# Tiny_Programmer.net
KiCad netlist of a schematic drawn in EAGLE
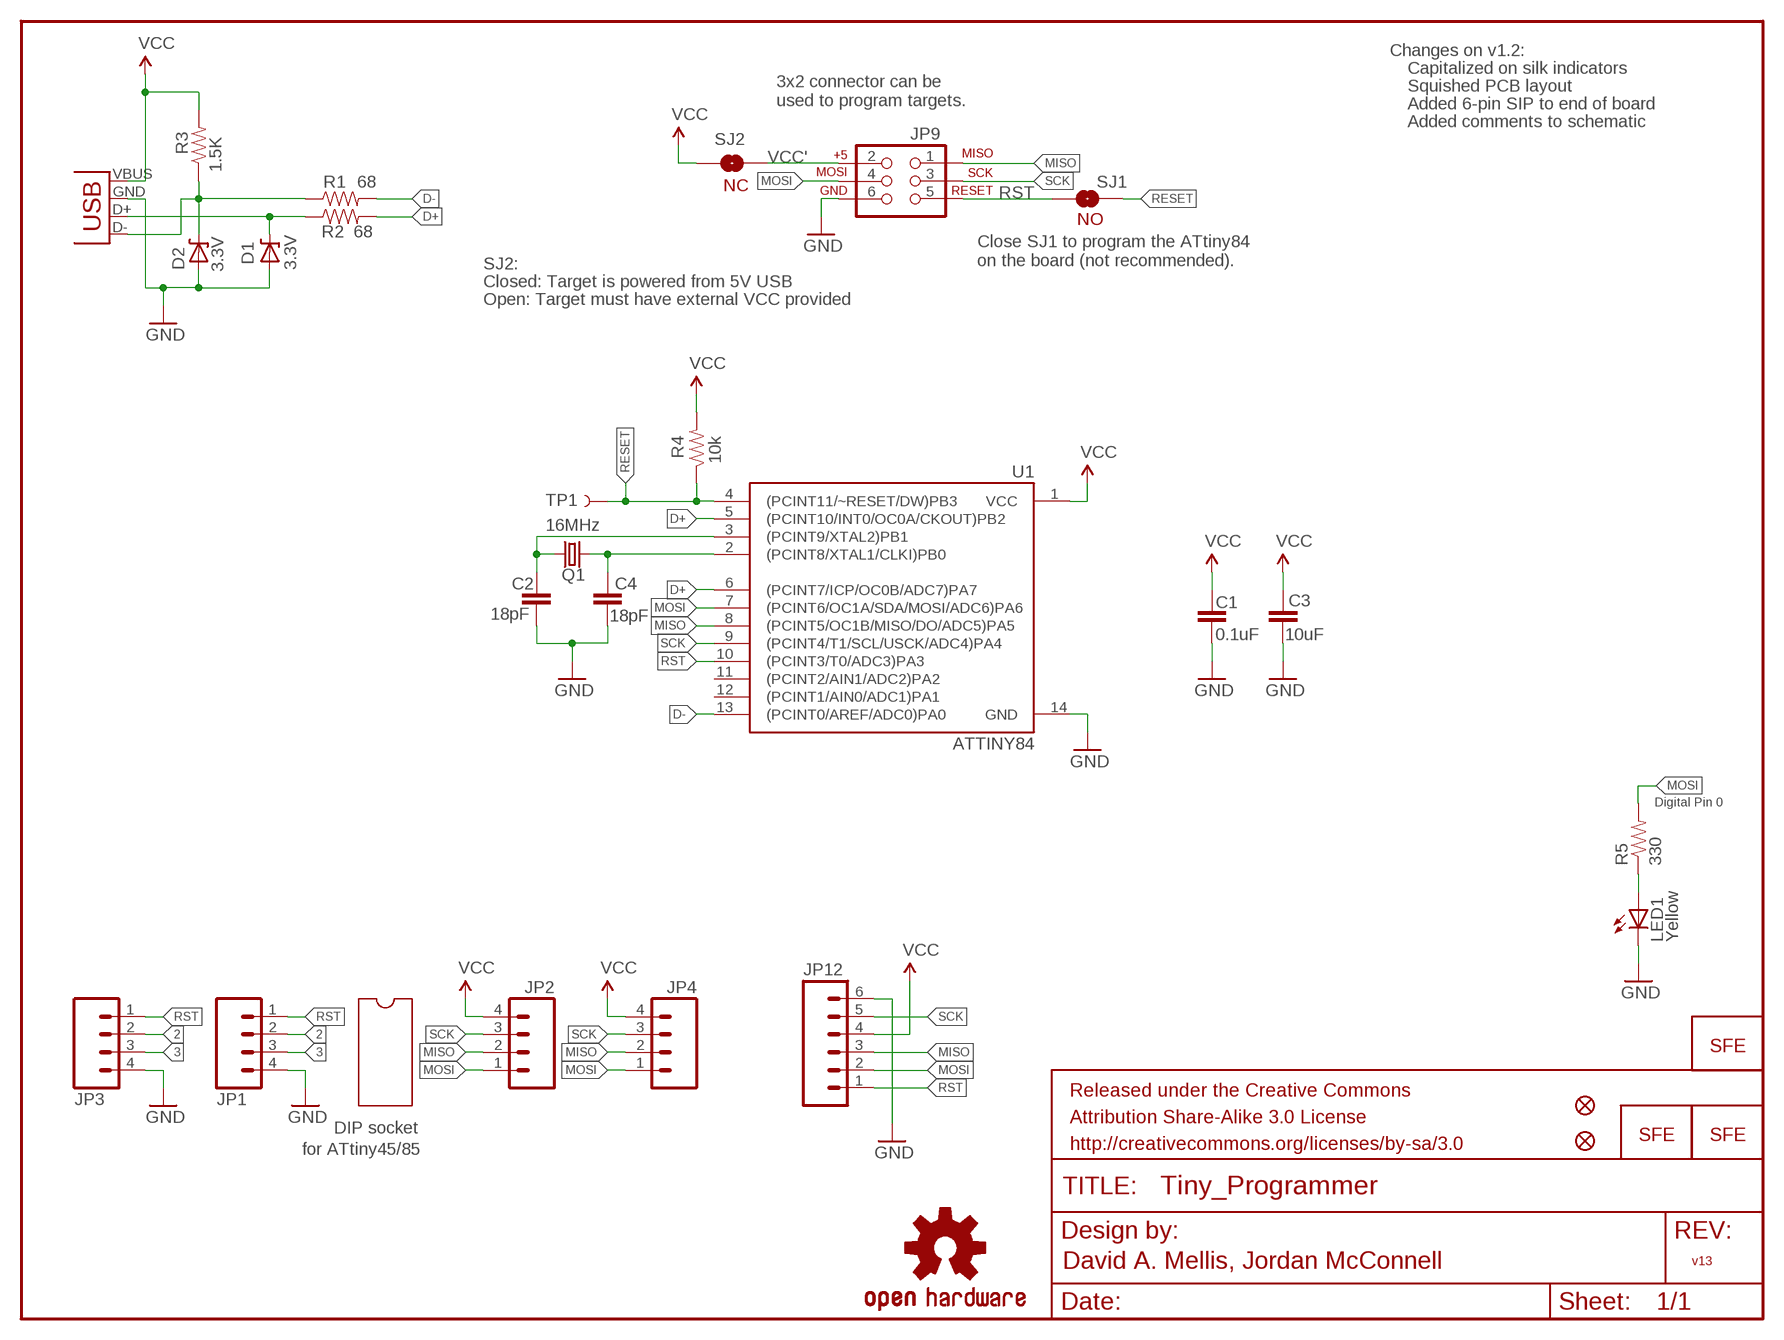
[diagram p0: schematic, sheet 1]

(export (version "E")
  (design (tool "Eeschema 10.0.6"))
  (components
    (comp (ref "C1")
      (value "0.1uF")
      (footprint "eagle-import:0402-CAP")
      (libsource (lib "eagle-import") (part "CAP0402-CAP"))
    )
    (comp (ref "C2")
      (value "18pF")
      (footprint "eagle-import:0402-CAP")
      (libsource (lib "eagle-import") (part "CAP0402-CAP"))
    )
    (comp (ref "C3")
      (value "10uF")
      (footprint "eagle-import:0402-CAP")
      (libsource (lib "eagle-import") (part "CAP0402-CAP"))
    )
    (comp (ref "C4")
      (value "18pF")
      (footprint "eagle-import:0402-CAP")
      (libsource (lib "eagle-import") (part "CAP0402-CAP"))
    )
    (comp (ref "D1")
      (value "3.3V")
      (footprint "eagle-import:SOD-323")
      (libsource (lib "eagle-import") (part "DIODE-ZENER-BZT52"))
    )
    (comp (ref "D2")
      (value "3.3V")
      (footprint "eagle-import:SOD-323")
      (libsource (lib "eagle-import") (part "DIODE-ZENER-BZT52"))
    )
    (comp (ref "FRAME1")
      (value "FRAME-LETTER")
      (footprint "eagle-import:CREATIVE_COMMONS")
      (libsource (lib "eagle-import") (part "FRAME-LETTER"))
    )
    (comp (ref "JP1")
      (value "M04PTH")
      (footprint "eagle-import:1X04")
      (libsource (lib "eagle-import") (part "M04PTH"))
    )
    (comp (ref "JP2")
      (value "M04PTH")
      (footprint "eagle-import:1X04")
      (libsource (lib "eagle-import") (part "M04PTH"))
    )
    (comp (ref "JP3")
      (value "M04SMD_STRAIGHT_COMBO")
      (footprint "eagle-import:1X04_SMD_STRAIGHT_COMBO")
      (libsource (lib "eagle-import") (part "M04SMD_STRAIGHT_COMBO"))
    )
    (comp (ref "JP4")
      (value "M04SMD_STRAIGHT_COMBO")
      (footprint "eagle-import:1X04_SMD_STRAIGHT_COMBO")
      (libsource (lib "eagle-import") (part "M04SMD_STRAIGHT_COMBO"))
    )
    (comp (ref "JP5")
      (value "LOGO-SFENW2")
      (footprint "eagle-import:SFE-NEW-WEB")
      (libsource (lib "eagle-import") (part "LOGO-SFENW2"))
    )
    (comp (ref "JP6")
      (value "LOGO-SFESK")
      (footprint "eagle-import:SFE-LOGO-FLAME")
      (libsource (lib "eagle-import") (part "LOGO-SFESK"))
    )
    (comp (ref "JP7")
      (value "FIDUCIALUFIDUCIAL")
      (footprint "eagle-import:MICRO-FIDUCIAL")
      (libsource (lib "eagle-import") (part "FIDUCIALUFIDUCIAL"))
    )
    (comp (ref "JP8")
      (value "FIDUCIALUFIDUCIAL")
      (footprint "eagle-import:MICRO-FIDUCIAL")
      (libsource (lib "eagle-import") (part "FIDUCIALUFIDUCIAL"))
    )
    (comp (ref "JP9")
      (value "AVR_SPI_PRG_6PTH")
      (footprint "eagle-import:2X3")
      (libsource (lib "eagle-import") (part "AVR_SPI_PRG_6PTH"))
    )
    (comp (ref "JP11")
      (value "LOGO-SFESK")
      (footprint "eagle-import:SFE-LOGO-FLAME")
      (libsource (lib "eagle-import") (part "LOGO-SFESK"))
    )
    (comp (ref "JP12")
      (value "M06SIP")
      (footprint "eagle-import:1X06")
      (libsource (lib "eagle-import") (part "M06SIP"))
    )
    (comp (ref "LED1")
      (value "Yellow")
      (footprint "eagle-import:LED-0603")
      (libsource (lib "eagle-import") (part "LED0603"))
    )
    (comp (ref "Q1")
      (value "16MHz")
      (footprint "eagle-import:CRYSTAL-SMD-5X3")
      (libsource (lib "eagle-import") (part "CRYSTAL5X3"))
    )
    (comp (ref "R1")
      (value "68")
      (footprint "eagle-import:0402-RES")
      (libsource (lib "eagle-import") (part "RESISTOR0402-RES"))
    )
    (comp (ref "R2")
      (value "68")
      (footprint "eagle-import:0402-RES")
      (libsource (lib "eagle-import") (part "RESISTOR0402-RES"))
    )
    (comp (ref "R3")
      (value "1.5K")
      (footprint "eagle-import:0402-RES")
      (libsource (lib "eagle-import") (part "RESISTOR0402-RES"))
    )
    (comp (ref "R4")
      (value "10k")
      (footprint "eagle-import:0402-RES")
      (libsource (lib "eagle-import") (part "RESISTOR0402-RES"))
    )
    (comp (ref "R5")
      (value "330")
      (footprint "eagle-import:0402-RES")
      (libsource (lib "eagle-import") (part "RESISTOR0402-RES"))
    )
    (comp (ref "SJ1")
      (value "SOLDERJUMPERNO")
      (footprint "eagle-import:SJ_2S-NO")
      (libsource (lib "eagle-import") (part "SOLDERJUMPERNO"))
    )
    (comp (ref "SJ2")
      (value "NC")
      (footprint "eagle-import:SJ_2S")
      (libsource (lib "eagle-import") (part "SOLDERJUMPERNC"))
    )
    (comp (ref "TP1")
      (value "TEST-POINT3")
      (footprint "eagle-import:PAD.03X.03")
      (libsource (lib "eagle-import") (part "TEST-POINT3"))
    )
    (comp (ref "U$1")
      (value "OSHW-LOGOS")
      (footprint "eagle-import:OSHW-LOGO-S")
      (libsource (lib "eagle-import") (part "OSHW-LOGOS"))
    )
    (comp (ref "U1")
      (value "ATTINY84")
      (footprint "eagle-import:SO14")
      (libsource (lib "eagle-import") (part "ATTINY84"))
    )
    (comp (ref "X1")
      (value "USB-A-H")
      (footprint "eagle-import:USB-A-H")
      (libsource (lib "eagle-import") (part "USB-A-H"))
    )
  )
  (nets
    (net (code "1") (name "/VCC'") (class "Default")
      (node (ref "JP9") (pin "2") (pinfunction "2_2") (pintype "passive"))
      (node (ref "SJ2") (pin "2") (pinfunction "2_2") (pintype "passive"))
    )
    (net (code "2") (name "2") (class "Default")
      (node (ref "JP1") (pin "2") (pinfunction "2_2") (pintype "passive"))
      (node (ref "JP3") (pin "2") (pinfunction "2_2") (pintype "passive"))
    )
    (net (code "3") (name "3") (class "Default")
      (node (ref "JP1") (pin "3") (pinfunction "3_3") (pintype "passive"))
      (node (ref "JP3") (pin "3") (pinfunction "3_3") (pintype "passive"))
    )
    (net (code "4") (name "D+") (class "Default")
      (node (ref "R2") (pin "2") (pinfunction "2_2") (pintype "passive"))
      (node (ref "U1") (pin "5") (pinfunction "(PCINT10/INT0/OC0A/CKOUT)PB2_5") (pintype "bidirectional"))
      (node (ref "U1") (pin "6") (pinfunction "(PCINT7/ICP/OC0B/ADC7)PA7_6") (pintype "bidirectional"))
    )
    (net (code "5") (name "D-") (class "Default")
      (node (ref "R1") (pin "2") (pinfunction "2_2") (pintype "passive"))
      (node (ref "U1") (pin "13") (pinfunction "(PCINT0/AREF/ADC0)PA0_13") (pintype "bidirectional"))
    )
    (net (code "6") (name "GND") (class "Default")
      (node (ref "C1") (pin "2") (pinfunction "2_2") (pintype "passive"))
      (node (ref "C2") (pin "2") (pinfunction "2_2") (pintype "passive"))
      (node (ref "C3") (pin "2") (pinfunction "2_2") (pintype "passive"))
      (node (ref "C4") (pin "2") (pinfunction "2_2") (pintype "passive"))
      (node (ref "D1") (pin "2") (pinfunction "A_2") (pintype "passive"))
      (node (ref "D2") (pin "2") (pinfunction "A_2") (pintype "passive"))
      (node (ref "JP1") (pin "4") (pinfunction "4_4") (pintype "passive"))
      (node (ref "JP12") (pin "6") (pinfunction "6_6") (pintype "passive"))
      (node (ref "JP3") (pin "4") (pinfunction "4_4") (pintype "passive"))
      (node (ref "JP9") (pin "6") (pinfunction "6_6") (pintype "passive"))
      (node (ref "LED1") (pin "C") (pinfunction "C_C") (pintype "passive"))
      (node (ref "U1") (pin "14") (pinfunction "GND_14") (pintype "bidirectional"))
      (node (ref "X1") (pin "GND") (pinfunction "VBUS_GND") (pintype "bidirectional"))
    )
    (net (code "7") (name "MISO") (class "Default")
      (node (ref "JP12") (pin "3") (pinfunction "3_3") (pintype "passive"))
      (node (ref "JP2") (pin "2") (pinfunction "2_2") (pintype "passive"))
      (node (ref "JP4") (pin "2") (pinfunction "2_2") (pintype "passive"))
      (node (ref "JP9") (pin "1") (pinfunction "1_1") (pintype "passive"))
      (node (ref "U1") (pin "8") (pinfunction "(PCINT5/OC1B/MISO/DO/ADC5)PA5_8") (pintype "bidirectional"))
    )
    (net (code "8") (name "MOSI") (class "Default")
      (node (ref "JP12") (pin "2") (pinfunction "2_2") (pintype "passive"))
      (node (ref "JP2") (pin "1") (pinfunction "1_1") (pintype "passive"))
      (node (ref "JP4") (pin "1") (pinfunction "1_1") (pintype "passive"))
      (node (ref "JP9") (pin "4") (pinfunction "4_4") (pintype "passive"))
      (node (ref "R5") (pin "2") (pinfunction "2_2") (pintype "passive"))
      (node (ref "U1") (pin "7") (pinfunction "(PCINT6/OC1A/SDA/MOSI/ADC6)PA6_7") (pintype "bidirectional"))
    )
    (net (code "9") (name "Net-(D1-C)") (class "Default")
      (node (ref "D1") (pin "1") (pinfunction "C_1") (pintype "passive"))
      (node (ref "R2") (pin "1") (pinfunction "1_1") (pintype "passive"))
      (node (ref "X1") (pin "D+") (pinfunction "D-_D+") (pintype "bidirectional"))
    )
    (net (code "10") (name "Net-(D2-C)") (class "Default")
      (node (ref "D2") (pin "1") (pinfunction "C_1") (pintype "passive"))
      (node (ref "R1") (pin "1") (pinfunction "1_1") (pintype "passive"))
      (node (ref "R3") (pin "1") (pinfunction "1_1") (pintype "passive"))
      (node (ref "X1") (pin "D-") (pinfunction "D+_D-") (pintype "bidirectional"))
    )
    (net (code "11") (name "Net-(LED1-PadA)") (class "Default")
      (node (ref "LED1") (pin "A") (pinfunction "A_A") (pintype "passive"))
      (node (ref "R5") (pin "1") (pinfunction "1_1") (pintype "passive"))
    )
    (net (code "12") (name "Net-(Q1-2)") (class "Default")
      (node (ref "C2") (pin "1") (pinfunction "1_1") (pintype "passive"))
      (node (ref "Q1") (pin "3") (pinfunction "2_3") (pintype "passive"))
      (node (ref "U1") (pin "3") (pinfunction "(PCINT9/XTAL2)PB1_3") (pintype "bidirectional"))
    )
    (net (code "13") (name "Net-(U1-(PCINT8{slash}XTAL1{slash}CLKI)PB0)") (class "Default")
      (node (ref "C4") (pin "1") (pinfunction "1_1") (pintype "passive"))
      (node (ref "Q1") (pin "1") (pinfunction "1_1") (pintype "passive"))
      (node (ref "U1") (pin "2") (pinfunction "(PCINT8/XTAL1/CLKI)PB0_2") (pintype "bidirectional"))
    )
    (net (code "14") (name "RESET") (class "Default")
      (node (ref "R4") (pin "1") (pinfunction "1_1") (pintype "passive"))
      (node (ref "SJ1") (pin "1") (pinfunction "1_1") (pintype "passive"))
      (node (ref "TP1") (pin "P$1") (pinfunction "1_P$1") (pintype "bidirectional"))
      (node (ref "U1") (pin "4") (pinfunction "(PCINT11/~{RESET/DW})PB3_4") (pintype "bidirectional"))
    )
    (net (code "15") (name "RST") (class "Default")
      (node (ref "JP1") (pin "1") (pinfunction "1_1") (pintype "passive"))
      (node (ref "JP12") (pin "1") (pinfunction "1_1") (pintype "passive"))
      (node (ref "JP3") (pin "1") (pinfunction "1_1") (pintype "passive"))
      (node (ref "JP9") (pin "5") (pinfunction "5_5") (pintype "passive"))
      (node (ref "SJ1") (pin "2") (pinfunction "2_2") (pintype "passive"))
      (node (ref "U1") (pin "10") (pinfunction "(PCINT3/T0/ADC3)PA3_10") (pintype "bidirectional"))
    )
    (net (code "16") (name "SCK") (class "Default")
      (node (ref "JP12") (pin "5") (pinfunction "5_5") (pintype "passive"))
      (node (ref "JP2") (pin "3") (pinfunction "3_3") (pintype "passive"))
      (node (ref "JP4") (pin "3") (pinfunction "3_3") (pintype "passive"))
      (node (ref "JP9") (pin "3") (pinfunction "3_3") (pintype "passive"))
      (node (ref "U1") (pin "9") (pinfunction "(PCINT4/T1/SCL/USCK/ADC4)PA4_9") (pintype "bidirectional"))
    )
    (net (code "17") (name "VCC") (class "Default")
      (node (ref "C1") (pin "1") (pinfunction "1_1") (pintype "passive"))
      (node (ref "C3") (pin "1") (pinfunction "1_1") (pintype "passive"))
      (node (ref "JP12") (pin "4") (pinfunction "4_4") (pintype "passive"))
      (node (ref "JP2") (pin "4") (pinfunction "4_4") (pintype "passive"))
      (node (ref "JP4") (pin "4") (pinfunction "4_4") (pintype "passive"))
      (node (ref "R3") (pin "2") (pinfunction "2_2") (pintype "passive"))
      (node (ref "R4") (pin "2") (pinfunction "2_2") (pintype "passive"))
      (node (ref "SJ2") (pin "1") (pinfunction "1_1") (pintype "passive"))
      (node (ref "U1") (pin "1") (pinfunction "VCC_1") (pintype "bidirectional"))
      (node (ref "X1") (pin "VBUS") (pinfunction "GND_VBUS") (pintype "bidirectional"))
    )
    (net (code "18") (name "unconnected-(U1-(PCINT1{slash}AIN0{slash}ADC1)PA1-Pad12)") (class "Default")
      (node (ref "U1") (pin "12") (pinfunction "(PCINT1/AIN0/ADC1)PA1_12") (pintype "bidirectional"))
    )
    (net (code "19") (name "unconnected-(U1-(PCINT2{slash}AIN1{slash}ADC2)PA2-Pad11)") (class "Default")
      (node (ref "U1") (pin "11") (pinfunction "(PCINT2/AIN1/ADC2)PA2_11") (pintype "bidirectional"))
    )
  )
)
